# shield.net
KiCad netlist of a schematic drawn in EAGLE
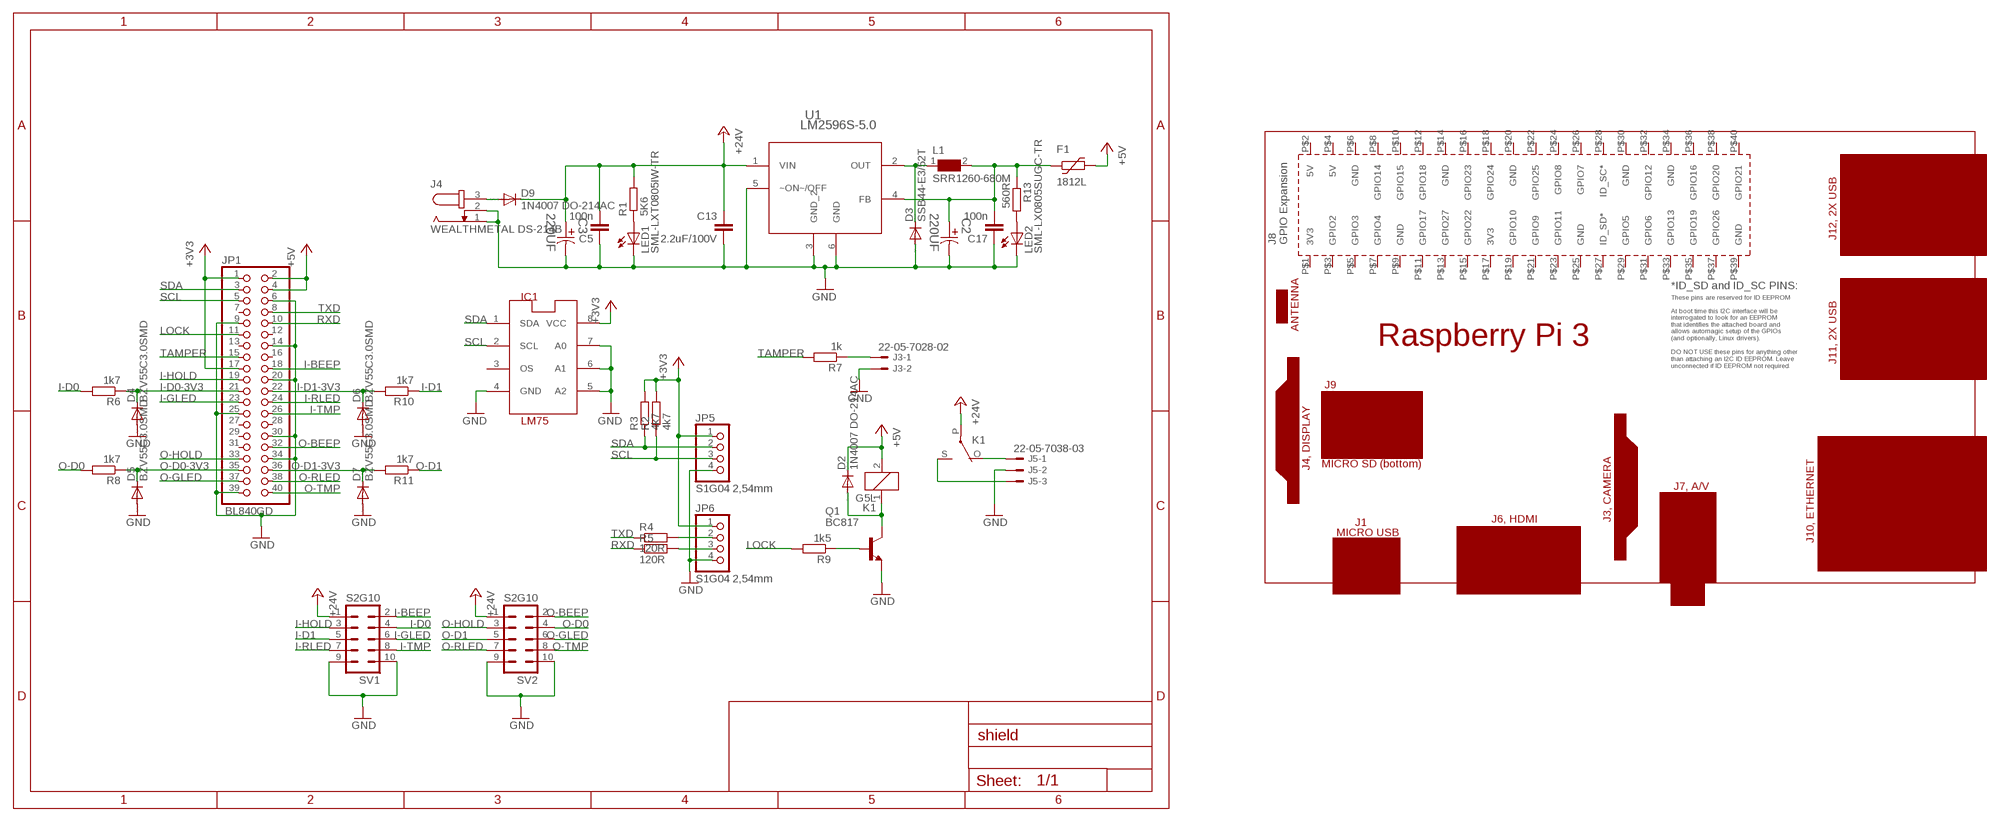
[diagram p0: schematic, sheet 1]

(export (version "E")
  (design (tool "Eeschema 10.0.6"))
  (components
    (comp (ref "C2")
      (value "220UF")
      (footprint "eagle-import:CAPAE830X1050N")
      (fields (field (name "MPN") "EEE-FP1V221AP") (field (name "TOLERANCE") "±20 %"))
      (libsource (lib "eagle-import") (part "EEE--CASE-FFP1V221AP"))
    )
    (comp (ref "C3")
      (value "220UF")
      (footprint "eagle-import:CAPAE830X1050N")
      (fields (field (name "MPN") "EEE-FP1V221AP") (field (name "TOLERANCE") "±20 %"))
      (libsource (lib "eagle-import") (part "EEE--CASE-FFP1V221AP"))
    )
    (comp (ref "C5")
      (value "100n")
      (footprint "eagle-import:C0805")
      (libsource (lib "eagle-import") (part "C-EUC0805"))
    )
    (comp (ref "C13")
      (value "2.2uF/100V")
      (footprint "eagle-import:C1206")
      (libsource (lib "eagle-import") (part "C-EUC1206"))
    )
    (comp (ref "C17")
      (value "100n")
      (footprint "eagle-import:C0805")
      (libsource (lib "eagle-import") (part "C-EUC0805"))
    )
    (comp (ref "D2")
      (value "1N4007 DO-214AC")
      (footprint "eagle-import:DO-214AC")
      (libsource (lib "eagle-import") (part "DIODE-DO-214AC"))
    )
    (comp (ref "D3")
      (value "SSB44-E3/52T")
      (footprint "eagle-import:DO214AA")
      (libsource (lib "eagle-import") (part "DIODE-DO214AA"))
    )
    (comp (ref "D4")
      (value "BZV55C3.0SMD")
      (footprint "eagle-import:MINIMELF")
      (libsource (lib "eagle-import") (part "DIODE-MINIMELF"))
    )
    (comp (ref "D5")
      (value "BZV55C3.0SMD")
      (footprint "eagle-import:MINIMELF")
      (libsource (lib "eagle-import") (part "DIODE-MINIMELF"))
    )
    (comp (ref "D6")
      (value "BZV55C3.0SMD")
      (footprint "eagle-import:MINIMELF")
      (libsource (lib "eagle-import") (part "DIODE-MINIMELF"))
    )
    (comp (ref "D7")
      (value "BZV55C3.0SMD")
      (footprint "eagle-import:MINIMELF")
      (libsource (lib "eagle-import") (part "DIODE-MINIMELF"))
    )
    (comp (ref "D9")
      (value "1N4007 DO-214AC")
      (footprint "eagle-import:DO-214AC")
      (libsource (lib "eagle-import") (part "DIODE-DO-214AC"))
    )
    (comp (ref "F1")
      (value "1812L")
      (footprint "eagle-import:1812L")
      (libsource (lib "eagle-import") (part "1812L"))
    )
    (comp (ref "IC1")
      (value "LM75")
      (footprint "eagle-import:SO8_LM75")
      (libsource (lib "eagle-import") (part "LM75_ICN"))
    )
    (comp (ref "J3")
      (value "22-05-7028-02")
      (footprint "eagle-import:7395-02")
      (libsource (lib "eagle-import") (part "22-?-0205-7028"))
    )
    (comp (ref "J4")
      (value "WEALTHMETAL DS-214B")
      (footprint "eagle-import:SPC4077")
      (libsource (lib "eagle-import") (part "JACK-PLUG0"))
    )
    (comp (ref "J5")
      (value "22-05-7038-03")
      (footprint "eagle-import:7395-03")
      (libsource (lib "eagle-import") (part "22-?-0305-7038"))
    )
    (comp (ref "JP1")
      (value "BL840GD")
      (footprint "eagle-import:2X20")
      (libsource (lib "eagle-import") (part "PINHD-2X20"))
    )
    (comp (ref "JP5")
      (value "S1G04 2,54mm")
      (footprint "eagle-import:1X04")
      (libsource (lib "eagle-import") (part "PINHD-1X4"))
    )
    (comp (ref "JP6")
      (value "S1G04 2,54mm")
      (footprint "eagle-import:1X04")
      (libsource (lib "eagle-import") (part "PINHD-1X4"))
    )
    (comp (ref "K1")
      (value "G5L")
      (footprint "eagle-import:G5LE")
      (libsource (lib "eagle-import") (part "G5L"))
    )
    (comp (ref "L1")
      (value "SRR1260-680M")
      (footprint "eagle-import:WE-PD_1260_1245_1280_1210")
      (fields (field (name "MPN") "7447709680"))
      (libsource (lib "eagle-import") (part "WE-PD_1260/1245/1280/1210-7447709680"))
    )
    (comp (ref "LED1")
      (value "SML-LXT0805IW-TR")
      (footprint "eagle-import:CHIPLED_0805")
      (libsource (lib "eagle-import") (part "LEDCHIPLED_0805"))
    )
    (comp (ref "LED2")
      (value "SML-LX0805SUGC-TR")
      (footprint "eagle-import:CHIPLED_0805")
      (libsource (lib "eagle-import") (part "LEDCHIPLED_0805"))
    )
    (comp (ref "PCB1")
      (value "RPI3")
      (footprint "eagle-import:RPI3")
      (libsource (lib "eagle-import") (part "RPI3"))
    )
    (comp (ref "Q1")
      (value "BC817")
      (footprint "eagle-import:SOT23-BEC")
      (libsource (lib "eagle-import") (part "-NPN-SOT23-BECBC817-16"))
    )
    (comp (ref "R1")
      (value "5K6")
      (footprint "eagle-import:R0805")
      (libsource (lib "eagle-import") (part "R-EU_R0805"))
    )
    (comp (ref "R2")
      (value "4k7")
      (footprint "eagle-import:R0805")
      (libsource (lib "eagle-import") (part "R-EU_R0805"))
    )
    (comp (ref "R3")
      (value "4k7")
      (footprint "eagle-import:R0805")
      (libsource (lib "eagle-import") (part "R-EU_R0805"))
    )
    (comp (ref "R4")
      (value "120R")
      (footprint "eagle-import:R0805")
      (libsource (lib "eagle-import") (part "R-EU_R0805"))
    )
    (comp (ref "R5")
      (value "120R")
      (footprint "eagle-import:R0805")
      (libsource (lib "eagle-import") (part "R-EU_R0805"))
    )
    (comp (ref "R6")
      (value "1k7")
      (footprint "eagle-import:R0805")
      (libsource (lib "eagle-import") (part "R-EU_R0805"))
    )
    (comp (ref "R7")
      (value "1k")
      (footprint "eagle-import:R0805")
      (libsource (lib "eagle-import") (part "R-EU_R0805"))
    )
    (comp (ref "R8")
      (value "1k7")
      (footprint "eagle-import:R0805")
      (libsource (lib "eagle-import") (part "R-EU_R0805"))
    )
    (comp (ref "R9")
      (value "1k5")
      (footprint "eagle-import:R0805")
      (libsource (lib "eagle-import") (part "R-EU_R0805"))
    )
    (comp (ref "R10")
      (value "1k7")
      (footprint "eagle-import:R0805")
      (libsource (lib "eagle-import") (part "R-EU_R0805"))
    )
    (comp (ref "R11")
      (value "1k7")
      (footprint "eagle-import:R0805")
      (libsource (lib "eagle-import") (part "R-EU_R0805"))
    )
    (comp (ref "R13")
      (value "560R")
      (footprint "eagle-import:R0805")
      (libsource (lib "eagle-import") (part "R-EU_R0805"))
    )
    (comp (ref "SV1")
      (value "S2G10")
      (footprint "eagle-import:MA05-2")
      (libsource (lib "eagle-import") (part "MA05-2"))
    )
    (comp (ref "SV2")
      (value "S2G10")
      (footprint "eagle-import:MA05-2")
      (libsource (lib "eagle-import") (part "MA05-2"))
    )
    (comp (ref "U1")
      (value "LM2596S-5.0")
      (footprint "eagle-import:TO170P1435X465-6N")
      (fields (field (name "MPN") "LM2596S-50"))
      (libsource (lib "eagle-import") (part "LM2596S-5.0"))
    )
  )
  (nets
    (net (code "1") (name "+3V3") (class "Default")
      (node (ref "IC1") (pin "8") (pinfunction "VCC_8") (pintype "power_in"))
      (node (ref "JP1") (pin "1") (pinfunction "1_1") (pintype "passive"))
      (node (ref "JP1") (pin "17") (pinfunction "17_17") (pintype "passive"))
      (node (ref "JP5") (pin "1") (pinfunction "1_1") (pintype "passive"))
      (node (ref "JP6") (pin "1") (pinfunction "1_1") (pintype "passive"))
      (node (ref "R2") (pin "2") (pinfunction "2_2") (pintype "passive"))
      (node (ref "R3") (pin "2") (pinfunction "2_2") (pintype "passive"))
    )
    (net (code "2") (name "+5V") (class "Default")
      (node (ref "D2") (pin "C") (pinfunction "C_C") (pintype "passive"))
      (node (ref "F1") (pin "P$2") (pinfunction "2_P$2") (pintype "passive"))
      (node (ref "JP1") (pin "2") (pinfunction "2_2") (pintype "passive"))
      (node (ref "JP1") (pin "4") (pinfunction "4_4") (pintype "passive"))
      (node (ref "K1") (pin "2") (pinfunction "2_2") (pintype "passive"))
    )
    (net (code "3") (name "+24V") (class "Default")
      (node (ref "C13") (pin "1") (pinfunction "1_1") (pintype "passive"))
      (node (ref "C3") (pin "1") (pinfunction "1_1") (pintype "passive"))
      (node (ref "C5") (pin "2") (pinfunction "2_2") (pintype "passive"))
      (node (ref "D9") (pin "C") (pinfunction "C_C") (pintype "passive"))
      (node (ref "K1") (pin "P") (pinfunction "P_P") (pintype "passive"))
      (node (ref "R1") (pin "2") (pinfunction "2_2") (pintype "passive"))
      (node (ref "SV1") (pin "1") (pinfunction "1_1") (pintype "passive"))
      (node (ref "SV2") (pin "1") (pinfunction "1_1") (pintype "passive"))
      (node (ref "U1") (pin "1") (pinfunction "VIN_1") (pintype "power_in"))
    )
    (net (code "4") (name "/I-BEEP") (class "Default")
      (node (ref "JP1") (pin "18") (pinfunction "18_18") (pintype "passive"))
      (node (ref "SV1") (pin "2") (pinfunction "2_2") (pintype "passive"))
    )
    (net (code "5") (name "/I-D0") (class "Default")
      (node (ref "R6") (pin "2") (pinfunction "2_2") (pintype "passive"))
      (node (ref "SV1") (pin "4") (pinfunction "4_4") (pintype "passive"))
    )
    (net (code "6") (name "/I-D0-3V3") (class "Default")
      (node (ref "D4") (pin "C") (pinfunction "C_C") (pintype "passive"))
      (node (ref "JP1") (pin "21") (pinfunction "21_21") (pintype "passive"))
      (node (ref "R6") (pin "1") (pinfunction "1_1") (pintype "passive"))
    )
    (net (code "7") (name "/I-D1") (class "Default")
      (node (ref "R10") (pin "1") (pinfunction "1_1") (pintype "passive"))
      (node (ref "SV1") (pin "5") (pinfunction "5_5") (pintype "passive"))
    )
    (net (code "8") (name "/I-D1-3V3") (class "Default")
      (node (ref "D6") (pin "C") (pinfunction "C_C") (pintype "passive"))
      (node (ref "JP1") (pin "22") (pinfunction "22_22") (pintype "passive"))
      (node (ref "R10") (pin "2") (pinfunction "2_2") (pintype "passive"))
    )
    (net (code "9") (name "/I-GLED") (class "Default")
      (node (ref "JP1") (pin "23") (pinfunction "23_23") (pintype "passive"))
      (node (ref "SV1") (pin "6") (pinfunction "6_6") (pintype "passive"))
    )
    (net (code "10") (name "/I-HOLD") (class "Default")
      (node (ref "JP1") (pin "19") (pinfunction "19_19") (pintype "passive"))
      (node (ref "SV1") (pin "3") (pinfunction "3_3") (pintype "passive"))
    )
    (net (code "11") (name "/I-RLED") (class "Default")
      (node (ref "JP1") (pin "24") (pinfunction "24_24") (pintype "passive"))
      (node (ref "SV1") (pin "7") (pinfunction "7_7") (pintype "passive"))
    )
    (net (code "12") (name "/I-TMP") (class "Default")
      (node (ref "JP1") (pin "26") (pinfunction "26_26") (pintype "passive"))
      (node (ref "SV1") (pin "8") (pinfunction "8_8") (pintype "passive"))
    )
    (net (code "13") (name "/LOCK") (class "Default")
      (node (ref "JP1") (pin "11") (pinfunction "11_11") (pintype "passive"))
      (node (ref "R9") (pin "2") (pinfunction "2_2") (pintype "passive"))
    )
    (net (code "14") (name "/O-BEEP") (class "Default")
      (node (ref "JP1") (pin "32") (pinfunction "32_32") (pintype "passive"))
      (node (ref "SV2") (pin "2") (pinfunction "2_2") (pintype "passive"))
    )
    (net (code "15") (name "/O-D0") (class "Default")
      (node (ref "R8") (pin "2") (pinfunction "2_2") (pintype "passive"))
      (node (ref "SV2") (pin "4") (pinfunction "4_4") (pintype "passive"))
    )
    (net (code "16") (name "/O-D0-3V3") (class "Default")
      (node (ref "D5") (pin "C") (pinfunction "C_C") (pintype "passive"))
      (node (ref "JP1") (pin "35") (pinfunction "35_35") (pintype "passive"))
      (node (ref "R8") (pin "1") (pinfunction "1_1") (pintype "passive"))
    )
    (net (code "17") (name "/O-D1") (class "Default")
      (node (ref "R11") (pin "1") (pinfunction "1_1") (pintype "passive"))
      (node (ref "SV2") (pin "5") (pinfunction "5_5") (pintype "passive"))
    )
    (net (code "18") (name "/O-D1-3V3") (class "Default")
      (node (ref "D7") (pin "C") (pinfunction "C_C") (pintype "passive"))
      (node (ref "JP1") (pin "36") (pinfunction "36_36") (pintype "passive"))
      (node (ref "R11") (pin "2") (pinfunction "2_2") (pintype "passive"))
    )
    (net (code "19") (name "/O-GLED") (class "Default")
      (node (ref "JP1") (pin "37") (pinfunction "37_37") (pintype "passive"))
      (node (ref "SV2") (pin "6") (pinfunction "6_6") (pintype "passive"))
    )
    (net (code "20") (name "/O-HOLD") (class "Default")
      (node (ref "JP1") (pin "33") (pinfunction "33_33") (pintype "passive"))
      (node (ref "SV2") (pin "3") (pinfunction "3_3") (pintype "passive"))
    )
    (net (code "21") (name "/O-RLED") (class "Default")
      (node (ref "JP1") (pin "38") (pinfunction "38_38") (pintype "passive"))
      (node (ref "SV2") (pin "7") (pinfunction "7_7") (pintype "passive"))
    )
    (net (code "22") (name "/O-TMP") (class "Default")
      (node (ref "JP1") (pin "40") (pinfunction "40_40") (pintype "passive"))
      (node (ref "SV2") (pin "8") (pinfunction "8_8") (pintype "passive"))
    )
    (net (code "23") (name "/RXD") (class "Default")
      (node (ref "JP1") (pin "10") (pinfunction "10_10") (pintype "passive"))
      (node (ref "R5") (pin "1") (pinfunction "1_1") (pintype "passive"))
    )
    (net (code "24") (name "/SCL") (class "Default")
      (node (ref "IC1") (pin "2") (pinfunction "SCL_2") (pintype "bidirectional"))
      (node (ref "JP1") (pin "5") (pinfunction "5_5") (pintype "passive"))
      (node (ref "JP5") (pin "3") (pinfunction "3_3") (pintype "passive"))
      (node (ref "R2") (pin "1") (pinfunction "1_1") (pintype "passive"))
    )
    (net (code "25") (name "/SDA") (class "Default")
      (node (ref "IC1") (pin "1") (pinfunction "SDA_1") (pintype "bidirectional"))
      (node (ref "JP1") (pin "3") (pinfunction "3_3") (pintype "passive"))
      (node (ref "JP5") (pin "2") (pinfunction "2_2") (pintype "passive"))
      (node (ref "R3") (pin "1") (pinfunction "1_1") (pintype "passive"))
    )
    (net (code "26") (name "/TAMPER") (class "Default")
      (node (ref "JP1") (pin "15") (pinfunction "15_15") (pintype "passive"))
      (node (ref "R7") (pin "2") (pinfunction "2_2") (pintype "passive"))
    )
    (net (code "27") (name "/TXD") (class "Default")
      (node (ref "JP1") (pin "8") (pinfunction "8_8") (pintype "passive"))
      (node (ref "R4") (pin "1") (pinfunction "1_1") (pintype "passive"))
    )
    (net (code "28") (name "GND") (class "Default")
      (node (ref "C13") (pin "2") (pinfunction "2_2") (pintype "passive"))
      (node (ref "C17") (pin "1") (pinfunction "1_1") (pintype "passive"))
      (node (ref "C2") (pin "2") (pinfunction "2_2") (pintype "passive"))
      (node (ref "C3") (pin "2") (pinfunction "2_2") (pintype "passive"))
      (node (ref "C5") (pin "1") (pinfunction "1_1") (pintype "passive"))
      (node (ref "D3") (pin "A") (pinfunction "A_A") (pintype "passive"))
      (node (ref "D4") (pin "A") (pinfunction "A_A") (pintype "passive"))
      (node (ref "D5") (pin "A") (pinfunction "A_A") (pintype "passive"))
      (node (ref "D6") (pin "A") (pinfunction "A_A") (pintype "passive"))
      (node (ref "D7") (pin "A") (pinfunction "A_A") (pintype "passive"))
      (node (ref "IC1") (pin "4") (pinfunction "GND_4") (pintype "power_in"))
      (node (ref "IC1") (pin "5") (pinfunction "A2_5") (pintype "input"))
      (node (ref "IC1") (pin "6") (pinfunction "A1_6") (pintype "input"))
      (node (ref "IC1") (pin "7") (pinfunction "A0_7") (pintype "input"))
      (node (ref "J3") (pin "2") (pinfunction "S_2") (pintype "passive"))
      (node (ref "J4") (pin "1") (pinfunction "1_1") (pintype "passive"))
      (node (ref "J4") (pin "2") (pinfunction "2_2") (pintype "passive"))
      (node (ref "J5") (pin "2") (pinfunction "S_2") (pintype "passive"))
      (node (ref "JP1") (pin "14") (pinfunction "14_14") (pintype "passive"))
      (node (ref "JP1") (pin "20") (pinfunction "20_20") (pintype "passive"))
      (node (ref "JP1") (pin "25") (pinfunction "25_25") (pintype "passive"))
      (node (ref "JP1") (pin "30") (pinfunction "30_30") (pintype "passive"))
      (node (ref "JP1") (pin "34") (pinfunction "34_34") (pintype "passive"))
      (node (ref "JP1") (pin "39") (pinfunction "39_39") (pintype "passive"))
      (node (ref "JP1") (pin "6") (pinfunction "6_6") (pintype "passive"))
      (node (ref "JP1") (pin "9") (pinfunction "9_9") (pintype "passive"))
      (node (ref "JP5") (pin "4") (pinfunction "4_4") (pintype "passive"))
      (node (ref "JP6") (pin "4") (pinfunction "4_4") (pintype "passive"))
      (node (ref "LED1") (pin "C") (pinfunction "C_C") (pintype "passive"))
      (node (ref "LED2") (pin "C") (pinfunction "C_C") (pintype "passive"))
      (node (ref "Q1") (pin "E") (pinfunction "E_E") (pintype "passive"))
      (node (ref "SV1") (pin "10") (pinfunction "10_10") (pintype "passive"))
      (node (ref "SV1") (pin "9") (pinfunction "9_9") (pintype "passive"))
      (node (ref "SV2") (pin "10") (pinfunction "10_10") (pintype "passive"))
      (node (ref "SV2") (pin "9") (pinfunction "9_9") (pintype "passive"))
      (node (ref "U1") (pin "3") (pinfunction "GND_2_3") (pintype "passive"))
      (node (ref "U1") (pin "5") (pinfunction "~{ON}/OFF_5") (pintype "input"))
      (node (ref "U1") (pin "6") (pinfunction "GND_6") (pintype "passive"))
    )
    (net (code "29") (name "Net-(D2-PadA)") (class "Default")
      (node (ref "D2") (pin "A") (pinfunction "A_A") (pintype "passive"))
      (node (ref "K1") (pin "1") (pinfunction "1_1") (pintype "passive"))
      (node (ref "Q1") (pin "C") (pinfunction "C_C") (pintype "passive"))
    )
    (net (code "30") (name "Net-(D9-PadA)") (class "Default")
      (node (ref "D9") (pin "A") (pinfunction "A_A") (pintype "passive"))
      (node (ref "J4") (pin "3") (pinfunction "3_3") (pintype "passive"))
    )
    (net (code "31") (name "Net-(F1-1)") (class "Default")
      (node (ref "C17") (pin "2") (pinfunction "2_2") (pintype "passive"))
      (node (ref "C2") (pin "1") (pinfunction "1_1") (pintype "passive"))
      (node (ref "F1") (pin "P$1") (pinfunction "1_P$1") (pintype "passive"))
      (node (ref "L1") (pin "2") (pinfunction "2_2") (pintype "passive"))
      (node (ref "R13") (pin "1") (pinfunction "1_1") (pintype "passive"))
      (node (ref "U1") (pin "4") (pinfunction "FB_4") (pintype "input"))
    )
    (net (code "32") (name "Net-(J3A-S)") (class "Default")
      (node (ref "J3") (pin "1") (pinfunction "S_1") (pintype "passive"))
      (node (ref "R7") (pin "1") (pinfunction "1_1") (pintype "passive"))
    )
    (net (code "33") (name "Net-(J5A-S)") (class "Default")
      (node (ref "J5") (pin "1") (pinfunction "S_1") (pintype "passive"))
      (node (ref "K1") (pin "O") (pinfunction "O_O") (pintype "passive"))
    )
    (net (code "34") (name "Net-(J5C-S)") (class "Default")
      (node (ref "J5") (pin "3") (pinfunction "S_3") (pintype "passive"))
      (node (ref "K1") (pin "S") (pinfunction "S_S") (pintype "passive"))
    )
    (net (code "35") (name "Net-(JP6-Pad2)") (class "Default")
      (node (ref "JP6") (pin "2") (pinfunction "2_2") (pintype "passive"))
      (node (ref "R4") (pin "2") (pinfunction "2_2") (pintype "passive"))
    )
    (net (code "36") (name "Net-(JP6-Pad3)") (class "Default")
      (node (ref "JP6") (pin "3") (pinfunction "3_3") (pintype "passive"))
      (node (ref "R5") (pin "2") (pinfunction "2_2") (pintype "passive"))
    )
    (net (code "37") (name "Net-(LED1-PadA)") (class "Default")
      (node (ref "LED1") (pin "A") (pinfunction "A_A") (pintype "passive"))
      (node (ref "R1") (pin "1") (pinfunction "1_1") (pintype "passive"))
    )
    (net (code "38") (name "Net-(LED2-PadA)") (class "Default")
      (node (ref "LED2") (pin "A") (pinfunction "A_A") (pintype "passive"))
      (node (ref "R13") (pin "2") (pinfunction "2_2") (pintype "passive"))
    )
    (net (code "39") (name "Net-(Q1-PadB)") (class "Default")
      (node (ref "Q1") (pin "B") (pinfunction "B_B") (pintype "passive"))
      (node (ref "R9") (pin "1") (pinfunction "1_1") (pintype "passive"))
    )
    (net (code "40") (name "Net-(U1-OUT)") (class "Default")
      (node (ref "D3") (pin "C") (pinfunction "C_C") (pintype "passive"))
      (node (ref "L1") (pin "1") (pinfunction "1_1") (pintype "passive"))
      (node (ref "U1") (pin "2") (pinfunction "OUT_2") (pintype "output"))
    )
    (net (code "41") (name "unconnected-(IC1-OS-Pad3)") (class "Default")
      (node (ref "IC1") (pin "3") (pinfunction "OS_3") (pintype "output"))
    )
    (net (code "42") (name "unconnected-(JP1-Pad7)") (class "Default")
      (node (ref "JP1") (pin "7") (pinfunction "7_7") (pintype "passive"))
    )
    (net (code "43") (name "unconnected-(JP1-Pad12)") (class "Default")
      (node (ref "JP1") (pin "12") (pinfunction "12_12") (pintype "passive"))
    )
    (net (code "44") (name "unconnected-(JP1-Pad13)") (class "Default")
      (node (ref "JP1") (pin "13") (pinfunction "13_13") (pintype "passive"))
    )
    (net (code "45") (name "unconnected-(JP1-Pad16)") (class "Default")
      (node (ref "JP1") (pin "16") (pinfunction "16_16") (pintype "passive"))
    )
    (net (code "46") (name "unconnected-(JP1-Pad27)") (class "Default")
      (node (ref "JP1") (pin "27") (pinfunction "27_27") (pintype "passive"))
    )
    (net (code "47") (name "unconnected-(JP1-Pad28)") (class "Default")
      (node (ref "JP1") (pin "28") (pinfunction "28_28") (pintype "passive"))
    )
    (net (code "48") (name "unconnected-(JP1-Pad29)") (class "Default")
      (node (ref "JP1") (pin "29") (pinfunction "29_29") (pintype "passive"))
    )
    (net (code "49") (name "unconnected-(JP1-Pad31)") (class "Default")
      (node (ref "JP1") (pin "31") (pinfunction "31_31") (pintype "passive"))
    )
    (net (code "50") (name "unconnected-(PCB1-3V3-PadP$1)") (class "Default")
      (node (ref "PCB1") (pin "P$1") (pinfunction "3V3_P$1") (pintype "bidirectional"))
    )
    (net (code "51") (name "unconnected-(PCB1-3V3-PadP$17)") (class "Default")
      (node (ref "PCB1") (pin "P$17") (pinfunction "3V3_P$17") (pintype "bidirectional"))
    )
    (net (code "52") (name "unconnected-(PCB1-5V-PadP$2)") (class "Default")
      (node (ref "PCB1") (pin "P$2") (pinfunction "5V_P$2") (pintype "bidirectional"))
    )
    (net (code "53") (name "unconnected-(PCB1-5V-PadP$4)") (class "Default")
      (node (ref "PCB1") (pin "P$4") (pinfunction "5V_P$4") (pintype "bidirectional"))
    )
    (net (code "54") (name "unconnected-(PCB1-GND-PadP$6)") (class "Default")
      (node (ref "PCB1") (pin "P$6") (pinfunction "GND_P$6") (pintype "bidirectional"))
    )
    (net (code "55") (name "unconnected-(PCB1-GND-PadP$9)") (class "Default")
      (node (ref "PCB1") (pin "P$9") (pinfunction "GND_P$9") (pintype "bidirectional"))
    )
    (net (code "56") (name "unconnected-(PCB1-GND-PadP$14)") (class "Default")
      (node (ref "PCB1") (pin "P$14") (pinfunction "GND_P$14") (pintype "bidirectional"))
    )
    (net (code "57") (name "unconnected-(PCB1-GND-PadP$20)") (class "Default")
      (node (ref "PCB1") (pin "P$20") (pinfunction "GND_P$20") (pintype "bidirectional"))
    )
    (net (code "58") (name "unconnected-(PCB1-GND-PadP$25)") (class "Default")
      (node (ref "PCB1") (pin "P$25") (pinfunction "GND_P$25") (pintype "bidirectional"))
    )
    (net (code "59") (name "unconnected-(PCB1-GND-PadP$30)") (class "Default")
      (node (ref "PCB1") (pin "P$30") (pinfunction "GND_P$30") (pintype "bidirectional"))
    )
    (net (code "60") (name "unconnected-(PCB1-GND-PadP$34)") (class "Default")
      (node (ref "PCB1") (pin "P$34") (pinfunction "GND_P$34") (pintype "bidirectional"))
    )
    (net (code "61") (name "unconnected-(PCB1-GND-PadP$39)") (class "Default")
      (node (ref "PCB1") (pin "P$39") (pinfunction "GND_P$39") (pintype "bidirectional"))
    )
    (net (code "62") (name "unconnected-(PCB1-GPIO2-PadP$3)") (class "Default")
      (node (ref "PCB1") (pin "P$3") (pinfunction "GPIO2_P$3") (pintype "bidirectional"))
    )
    (net (code "63") (name "unconnected-(PCB1-GPIO3-PadP$5)") (class "Default")
      (node (ref "PCB1") (pin "P$5") (pinfunction "GPIO3_P$5") (pintype "bidirectional"))
    )
    (net (code "64") (name "unconnected-(PCB1-GPIO4-PadP$7)") (class "Default")
      (node (ref "PCB1") (pin "P$7") (pinfunction "GPIO4_P$7") (pintype "bidirectional"))
    )
    (net (code "65") (name "unconnected-(PCB1-GPIO5-PadP$29)") (class "Default")
      (node (ref "PCB1") (pin "P$29") (pinfunction "GPIO5_P$29") (pintype "bidirectional"))
    )
    (net (code "66") (name "unconnected-(PCB1-GPIO6-PadP$31)") (class "Default")
      (node (ref "PCB1") (pin "P$31") (pinfunction "GPIO6_P$31") (pintype "bidirectional"))
    )
    (net (code "67") (name "unconnected-(PCB1-GPIO7-PadP$26)") (class "Default")
      (node (ref "PCB1") (pin "P$26") (pinfunction "GPIO7_P$26") (pintype "bidirectional"))
    )
    (net (code "68") (name "unconnected-(PCB1-GPIO8-PadP$24)") (class "Default")
      (node (ref "PCB1") (pin "P$24") (pinfunction "GPIO8_P$24") (pintype "bidirectional"))
    )
    (net (code "69") (name "unconnected-(PCB1-GPIO9-PadP$21)") (class "Default")
      (node (ref "PCB1") (pin "P$21") (pinfunction "GPIO9_P$21") (pintype "bidirectional"))
    )
    (net (code "70") (name "unconnected-(PCB1-GPIO10-PadP$19)") (class "Default")
      (node (ref "PCB1") (pin "P$19") (pinfunction "GPIO10_P$19") (pintype "bidirectional"))
    )
    (net (code "71") (name "unconnected-(PCB1-GPIO11-PadP$23)") (class "Default")
      (node (ref "PCB1") (pin "P$23") (pinfunction "GPIO11_P$23") (pintype "bidirectional"))
    )
    (net (code "72") (name "unconnected-(PCB1-GPIO12-PadP$32)") (class "Default")
      (node (ref "PCB1") (pin "P$32") (pinfunction "GPIO12_P$32") (pintype "bidirectional"))
    )
    (net (code "73") (name "unconnected-(PCB1-GPIO13-PadP$33)") (class "Default")
      (node (ref "PCB1") (pin "P$33") (pinfunction "GPIO13_P$33") (pintype "bidirectional"))
    )
    (net (code "74") (name "unconnected-(PCB1-GPIO14-PadP$8)") (class "Default")
      (node (ref "PCB1") (pin "P$8") (pinfunction "GPIO14_P$8") (pintype "bidirectional"))
    )
    (net (code "75") (name "unconnected-(PCB1-GPIO15-PadP$10)") (class "Default")
      (node (ref "PCB1") (pin "P$10") (pinfunction "GPIO15_P$10") (pintype "bidirectional"))
    )
    (net (code "76") (name "unconnected-(PCB1-GPIO16-PadP$36)") (class "Default")
      (node (ref "PCB1") (pin "P$36") (pinfunction "GPIO16_P$36") (pintype "bidirectional"))
    )
    (net (code "77") (name "unconnected-(PCB1-GPIO17-PadP$11)") (class "Default")
      (node (ref "PCB1") (pin "P$11") (pinfunction "GPIO17_P$11") (pintype "bidirectional"))
    )
    (net (code "78") (name "unconnected-(PCB1-GPIO18-PadP$12)") (class "Default")
      (node (ref "PCB1") (pin "P$12") (pinfunction "GPIO18_P$12") (pintype "bidirectional"))
    )
    (net (code "79") (name "unconnected-(PCB1-GPIO19-PadP$35)") (class "Default")
      (node (ref "PCB1") (pin "P$35") (pinfunction "GPIO19_P$35") (pintype "bidirectional"))
    )
    (net (code "80") (name "unconnected-(PCB1-GPIO20-PadP$38)") (class "Default")
      (node (ref "PCB1") (pin "P$38") (pinfunction "GPIO20_P$38") (pintype "bidirectional"))
    )
    (net (code "81") (name "unconnected-(PCB1-GPIO21-PadP$40)") (class "Default")
      (node (ref "PCB1") (pin "P$40") (pinfunction "GPIO21_P$40") (pintype "bidirectional"))
    )
    (net (code "82") (name "unconnected-(PCB1-GPIO22-PadP$15)") (class "Default")
      (node (ref "PCB1") (pin "P$15") (pinfunction "GPIO22_P$15") (pintype "bidirectional"))
    )
    (net (code "83") (name "unconnected-(PCB1-GPIO23-PadP$16)") (class "Default")
      (node (ref "PCB1") (pin "P$16") (pinfunction "GPIO23_P$16") (pintype "bidirectional"))
    )
    (net (code "84") (name "unconnected-(PCB1-GPIO24-PadP$18)") (class "Default")
      (node (ref "PCB1") (pin "P$18") (pinfunction "GPIO24_P$18") (pintype "bidirectional"))
    )
    (net (code "85") (name "unconnected-(PCB1-GPIO25-PadP$22)") (class "Default")
      (node (ref "PCB1") (pin "P$22") (pinfunction "GPIO25_P$22") (pintype "bidirectional"))
    )
    (net (code "86") (name "unconnected-(PCB1-GPIO26-PadP$37)") (class "Default")
      (node (ref "PCB1") (pin "P$37") (pinfunction "GPIO26_P$37") (pintype "bidirectional"))
    )
    (net (code "87") (name "unconnected-(PCB1-GPIO27-PadP$13)") (class "Default")
      (node (ref "PCB1") (pin "P$13") (pinfunction "GPIO27_P$13") (pintype "bidirectional"))
    )
    (net (code "88") (name "unconnected-(PCB1-ID_SC*-PadP$28)") (class "Default")
      (node (ref "PCB1") (pin "P$28") (pinfunction "ID_SC*_P$28") (pintype "bidirectional"))
    )
    (net (code "89") (name "unconnected-(PCB1-ID_SD*-PadP$27)") (class "Default")
      (node (ref "PCB1") (pin "P$27") (pinfunction "ID_SD*_P$27") (pintype "bidirectional"))
    )
  )
)
